# SchemaEletrica.net
KiCad netlist of a schematic drawn in EAGLE
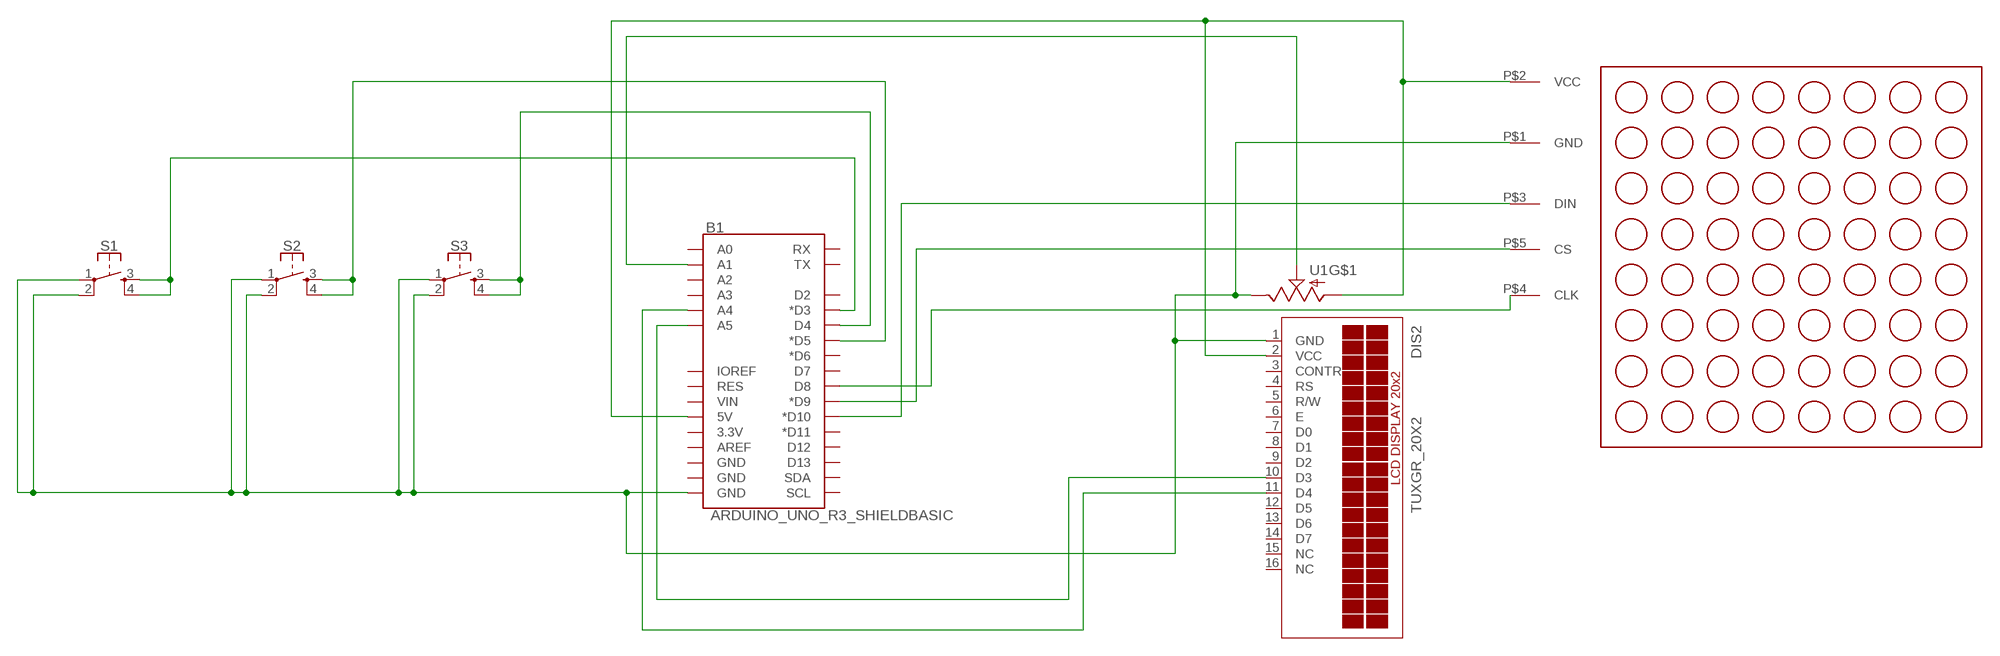
[diagram p0: schematic, sheet 1]

(export (version "E")
  (design (tool "Eeschema 10.0.6"))
  (components
    (comp (ref "B1")
      (value "ARDUINO_UNO_R3_SHIELDBASIC")
      (footprint "eagle-import:UNO_R3_SHIELD")
      (libsource (lib "eagle-import") (part "ARDUINO_UNO_R3_SHIELDBASIC"))
    )
    (comp (ref "DIS2")
      (value "TUXGR_20X2")
      (footprint "eagle-import:TUXGR_20X2")
      (libsource (lib "eagle-import") (part "TUXGR_20X2"))
    )
    (comp (ref "S1")
      (value "SPARKFUN-SWITCHES_MOMENTARY-SWITCH-SPST-2-SMD-4.6X2.8MM")
      (footprint "eagle-import:SPARKFUN-SWITCHES_TACTILE_SWITCH_SMD_4.6X2.8MM")
      (libsource (lib "eagle-import") (part "SPARKFUN-SWITCHES_MOMENTARY-SWITCH-SPST-2-SMD-4.6X2.8MM"))
    )
    (comp (ref "S2")
      (value "SPARKFUN-SWITCHES_MOMENTARY-SWITCH-SPST-2-SMD-4.6X2.8MM")
      (footprint "eagle-import:SPARKFUN-SWITCHES_TACTILE_SWITCH_SMD_4.6X2.8MM")
      (libsource (lib "eagle-import") (part "SPARKFUN-SWITCHES_MOMENTARY-SWITCH-SPST-2-SMD-4.6X2.8MM"))
    )
    (comp (ref "S3")
      (value "SPARKFUN-SWITCHES_MOMENTARY-SWITCH-SPST-2-SMD-4.6X2.8MM")
      (footprint "eagle-import:SPARKFUN-SWITCHES_TACTILE_SWITCH_SMD_4.6X2.8MM")
      (libsource (lib "eagle-import") (part "SPARKFUN-SWITCHES_MOMENTARY-SWITCH-SPST-2-SMD-4.6X2.8MM"))
    )
    (comp (ref "U$1")
      (value "RGB_MAT")
      (footprint "eagle-import:LED_MAT")
      (libsource (lib "eagle-import") (part "RGB_MAT"))
    )
    (comp (ref "U1")
      (value "POT_SWITCHPOT_PTH")
      (footprint "eagle-import:POT_PTH")
      (libsource (lib "eagle-import") (part "POT_SWITCHPOT_PTH"))
    )
  )
  (nets
    (net (code "1") (name "Net-(B1-*D3)") (class "Default")
      (node (ref "B1") (pin "D3") (pinfunction "*D3_D3") (pintype "bidirectional"))
      (node (ref "S1") (pin "3") (pinfunction "3_3") (pintype "passive"))
      (node (ref "S1") (pin "4") (pinfunction "4_4") (pintype "passive"))
    )
    (net (code "2") (name "Net-(B1-*D5)") (class "Default")
      (node (ref "B1") (pin "D5") (pinfunction "*D5_D5") (pintype "bidirectional"))
      (node (ref "S2") (pin "3") (pinfunction "3_3") (pintype "passive"))
      (node (ref "S2") (pin "4") (pinfunction "4_4") (pintype "passive"))
    )
    (net (code "3") (name "Net-(B1-*D9)") (class "Default")
      (node (ref "B1") (pin "D9") (pinfunction "*D9_D9") (pintype "bidirectional"))
      (node (ref "U$1") (pin "P$5") (pinfunction "CS_P$5") (pintype "bidirectional"))
    )
    (net (code "4") (name "Net-(B1-*D10)") (class "Default")
      (node (ref "B1") (pin "D10") (pinfunction "*D10_D10") (pintype "bidirectional"))
      (node (ref "U$1") (pin "P$3") (pinfunction "DIN_P$3") (pintype "bidirectional"))
    )
    (net (code "5") (name "Net-(B1-PadD4)") (class "Default")
      (node (ref "B1") (pin "D4") (pinfunction "D4_D4") (pintype "bidirectional"))
      (node (ref "S3") (pin "3") (pinfunction "3_3") (pintype "passive"))
      (node (ref "S3") (pin "4") (pinfunction "4_4") (pintype "passive"))
    )
    (net (code "6") (name "Net-(DIS2-D3)") (class "Default")
      (node (ref "B1") (pin "A5") (pinfunction "A5_A5") (pintype "bidirectional"))
      (node (ref "DIS2") (pin "10") (pinfunction "D3_10") (pintype "input"))
    )
    (net (code "7") (name "Net-(DIS2-D4)") (class "Default")
      (node (ref "B1") (pin "A4") (pinfunction "A4_A4") (pintype "bidirectional"))
      (node (ref "DIS2") (pin "11") (pinfunction "D4_11") (pintype "input"))
    )
    (net (code "8") (name "Net-(DIS2-GND)") (class "Default")
      (node (ref "B1") (pin "GND@0") (pinfunction "GND_GND@0") (pintype "bidirectional"))
      (node (ref "DIS2") (pin "1") (pinfunction "GND_1") (pintype "power_in"))
      (node (ref "S1") (pin "1") (pinfunction "1_1") (pintype "passive"))
      (node (ref "S1") (pin "2") (pinfunction "2_2") (pintype "passive"))
      (node (ref "S2") (pin "1") (pinfunction "1_1") (pintype "passive"))
      (node (ref "S2") (pin "2") (pinfunction "2_2") (pintype "passive"))
      (node (ref "S3") (pin "1") (pinfunction "1_1") (pintype "passive"))
      (node (ref "S3") (pin "2") (pinfunction "2_2") (pintype "passive"))
      (node (ref "U$1") (pin "P$1") (pinfunction "GND_P$1") (pintype "bidirectional"))
      (node (ref "U1") (pin "E@2") (pinfunction "E_E@2") (pintype "passive"))
    )
    (net (code "9") (name "Net-(DIS2-VCC)") (class "Default")
      (node (ref "B1") (pin "5V") (pinfunction "5V_5V") (pintype "bidirectional"))
      (node (ref "DIS2") (pin "2") (pinfunction "VCC_2") (pintype "power_in"))
      (node (ref "U$1") (pin "P$2") (pinfunction "VCC_P$2") (pintype "bidirectional"))
      (node (ref "U1") (pin "E@1") (pinfunction "A_E@1") (pintype "passive"))
    )
    (net (code "10") (name "Net-(U$1-CLK)") (class "Default")
      (node (ref "B1") (pin "D8") (pinfunction "D8_D8") (pintype "bidirectional"))
      (node (ref "U$1") (pin "P$4") (pinfunction "CLK_P$4") (pintype "bidirectional"))
    )
    (net (code "11") (name "Net-(U1A-S)") (class "Default")
      (node (ref "B1") (pin "A1") (pinfunction "A1_A1") (pintype "bidirectional"))
      (node (ref "U1") (pin "WAND") (pinfunction "S_WAND") (pintype "passive"))
    )
    (net (code "12") (name "unconnected-(B1-*D6-PadD6)") (class "Default")
      (node (ref "B1") (pin "D6") (pinfunction "*D6_D6") (pintype "bidirectional"))
    )
    (net (code "13") (name "unconnected-(B1-*D11-PadD11)") (class "Default")
      (node (ref "B1") (pin "D11") (pinfunction "*D11_D11") (pintype "bidirectional"))
    )
    (net (code "14") (name "unconnected-(B1-GND-PadGND@1)") (class "Default")
      (node (ref "B1") (pin "GND@1") (pinfunction "GND_GND@1") (pintype "bidirectional"))
    )
    (net (code "15") (name "unconnected-(B1-GND-PadGND@2)") (class "Default")
      (node (ref "B1") (pin "GND@2") (pinfunction "GND_GND@2") (pintype "bidirectional"))
    )
    (net (code "16") (name "unconnected-(B1-Pad3.3V)") (class "Default")
      (node (ref "B1") (pin "3.3V") (pinfunction "3.3V_3.3V") (pintype "bidirectional"))
    )
    (net (code "17") (name "unconnected-(B1-PadA0)") (class "Default")
      (node (ref "B1") (pin "A0") (pinfunction "A0_A0") (pintype "bidirectional"))
    )
    (net (code "18") (name "unconnected-(B1-PadA2)") (class "Default")
      (node (ref "B1") (pin "A2") (pinfunction "A2_A2") (pintype "bidirectional"))
    )
    (net (code "19") (name "unconnected-(B1-PadA3)") (class "Default")
      (node (ref "B1") (pin "A3") (pinfunction "A3_A3") (pintype "bidirectional"))
    )
    (net (code "20") (name "unconnected-(B1-PadAREF)") (class "Default")
      (node (ref "B1") (pin "AREF") (pinfunction "AREF_AREF") (pintype "bidirectional"))
    )
    (net (code "21") (name "unconnected-(B1-PadD2)") (class "Default")
      (node (ref "B1") (pin "D2") (pinfunction "D2_D2") (pintype "bidirectional"))
    )
    (net (code "22") (name "unconnected-(B1-PadD7)") (class "Default")
      (node (ref "B1") (pin "D7") (pinfunction "D7_D7") (pintype "bidirectional"))
    )
    (net (code "23") (name "unconnected-(B1-PadD12)") (class "Default")
      (node (ref "B1") (pin "D12") (pinfunction "D12_D12") (pintype "bidirectional"))
    )
    (net (code "24") (name "unconnected-(B1-PadD13)") (class "Default")
      (node (ref "B1") (pin "D13") (pinfunction "D13_D13") (pintype "bidirectional"))
    )
    (net (code "25") (name "unconnected-(B1-PadIOREF)") (class "Default")
      (node (ref "B1") (pin "IOREF") (pinfunction "IOREF_IOREF") (pintype "bidirectional"))
    )
    (net (code "26") (name "unconnected-(B1-PadRES)") (class "Default")
      (node (ref "B1") (pin "RES") (pinfunction "RES_RES") (pintype "bidirectional"))
    )
    (net (code "27") (name "unconnected-(B1-PadRX)") (class "Default")
      (node (ref "B1") (pin "RX") (pinfunction "RX_RX") (pintype "bidirectional"))
    )
    (net (code "28") (name "unconnected-(B1-PadSCL)") (class "Default")
      (node (ref "B1") (pin "SCL") (pinfunction "SCL_SCL") (pintype "bidirectional"))
    )
    (net (code "29") (name "unconnected-(B1-PadSDA)") (class "Default")
      (node (ref "B1") (pin "SDA") (pinfunction "SDA_SDA") (pintype "bidirectional"))
    )
    (net (code "30") (name "unconnected-(B1-PadTX)") (class "Default")
      (node (ref "B1") (pin "TX") (pinfunction "TX_TX") (pintype "bidirectional"))
    )
    (net (code "31") (name "unconnected-(B1-PadVIN)") (class "Default")
      (node (ref "B1") (pin "VIN") (pinfunction "VIN_VIN") (pintype "bidirectional"))
    )
    (net (code "32") (name "unconnected-(DIS2-CONTR-Pad3)") (class "Default")
      (node (ref "DIS2") (pin "3") (pinfunction "CONTR_3") (pintype "input"))
    )
    (net (code "33") (name "unconnected-(DIS2-D0-Pad7)") (class "Default")
      (node (ref "DIS2") (pin "7") (pinfunction "D0_7") (pintype "input"))
    )
    (net (code "34") (name "unconnected-(DIS2-D1-Pad8)") (class "Default")
      (node (ref "DIS2") (pin "8") (pinfunction "D1_8") (pintype "input"))
    )
    (net (code "35") (name "unconnected-(DIS2-D2-Pad9)") (class "Default")
      (node (ref "DIS2") (pin "9") (pinfunction "D2_9") (pintype "input"))
    )
    (net (code "36") (name "unconnected-(DIS2-D5-Pad12)") (class "Default")
      (node (ref "DIS2") (pin "12") (pinfunction "D5_12") (pintype "input"))
    )
    (net (code "37") (name "unconnected-(DIS2-D6-Pad13)") (class "Default")
      (node (ref "DIS2") (pin "13") (pinfunction "D6_13") (pintype "input"))
    )
    (net (code "38") (name "unconnected-(DIS2-D7-Pad14)") (class "Default")
      (node (ref "DIS2") (pin "14") (pinfunction "D7_14") (pintype "input"))
    )
    (net (code "39") (name "unconnected-(DIS2-E-Pad6)") (class "Default")
      (node (ref "DIS2") (pin "6") (pinfunction "E_6") (pintype "input"))
    )
    (net (code "40") (name "unconnected-(DIS2-NC-Pad15)") (class "Default")
      (node (ref "DIS2") (pin "15") (pinfunction "NC_15") (pintype "no_connect"))
    )
    (net (code "41") (name "unconnected-(DIS2-NC-Pad16)") (class "Default")
      (node (ref "DIS2") (pin "16") (pinfunction "NC_16") (pintype "no_connect"))
    )
    (net (code "42") (name "unconnected-(DIS2-RS-Pad4)") (class "Default")
      (node (ref "DIS2") (pin "4") (pinfunction "RS_4") (pintype "input"))
    )
    (net (code "43") (name "unconnected-(DIS2-R{slash}W-Pad5)") (class "Default")
      (node (ref "DIS2") (pin "5") (pinfunction "R/W_5") (pintype "input"))
    )
  )
)
